# integrate.net
KiCad netlist of a schematic drawn in EAGLE
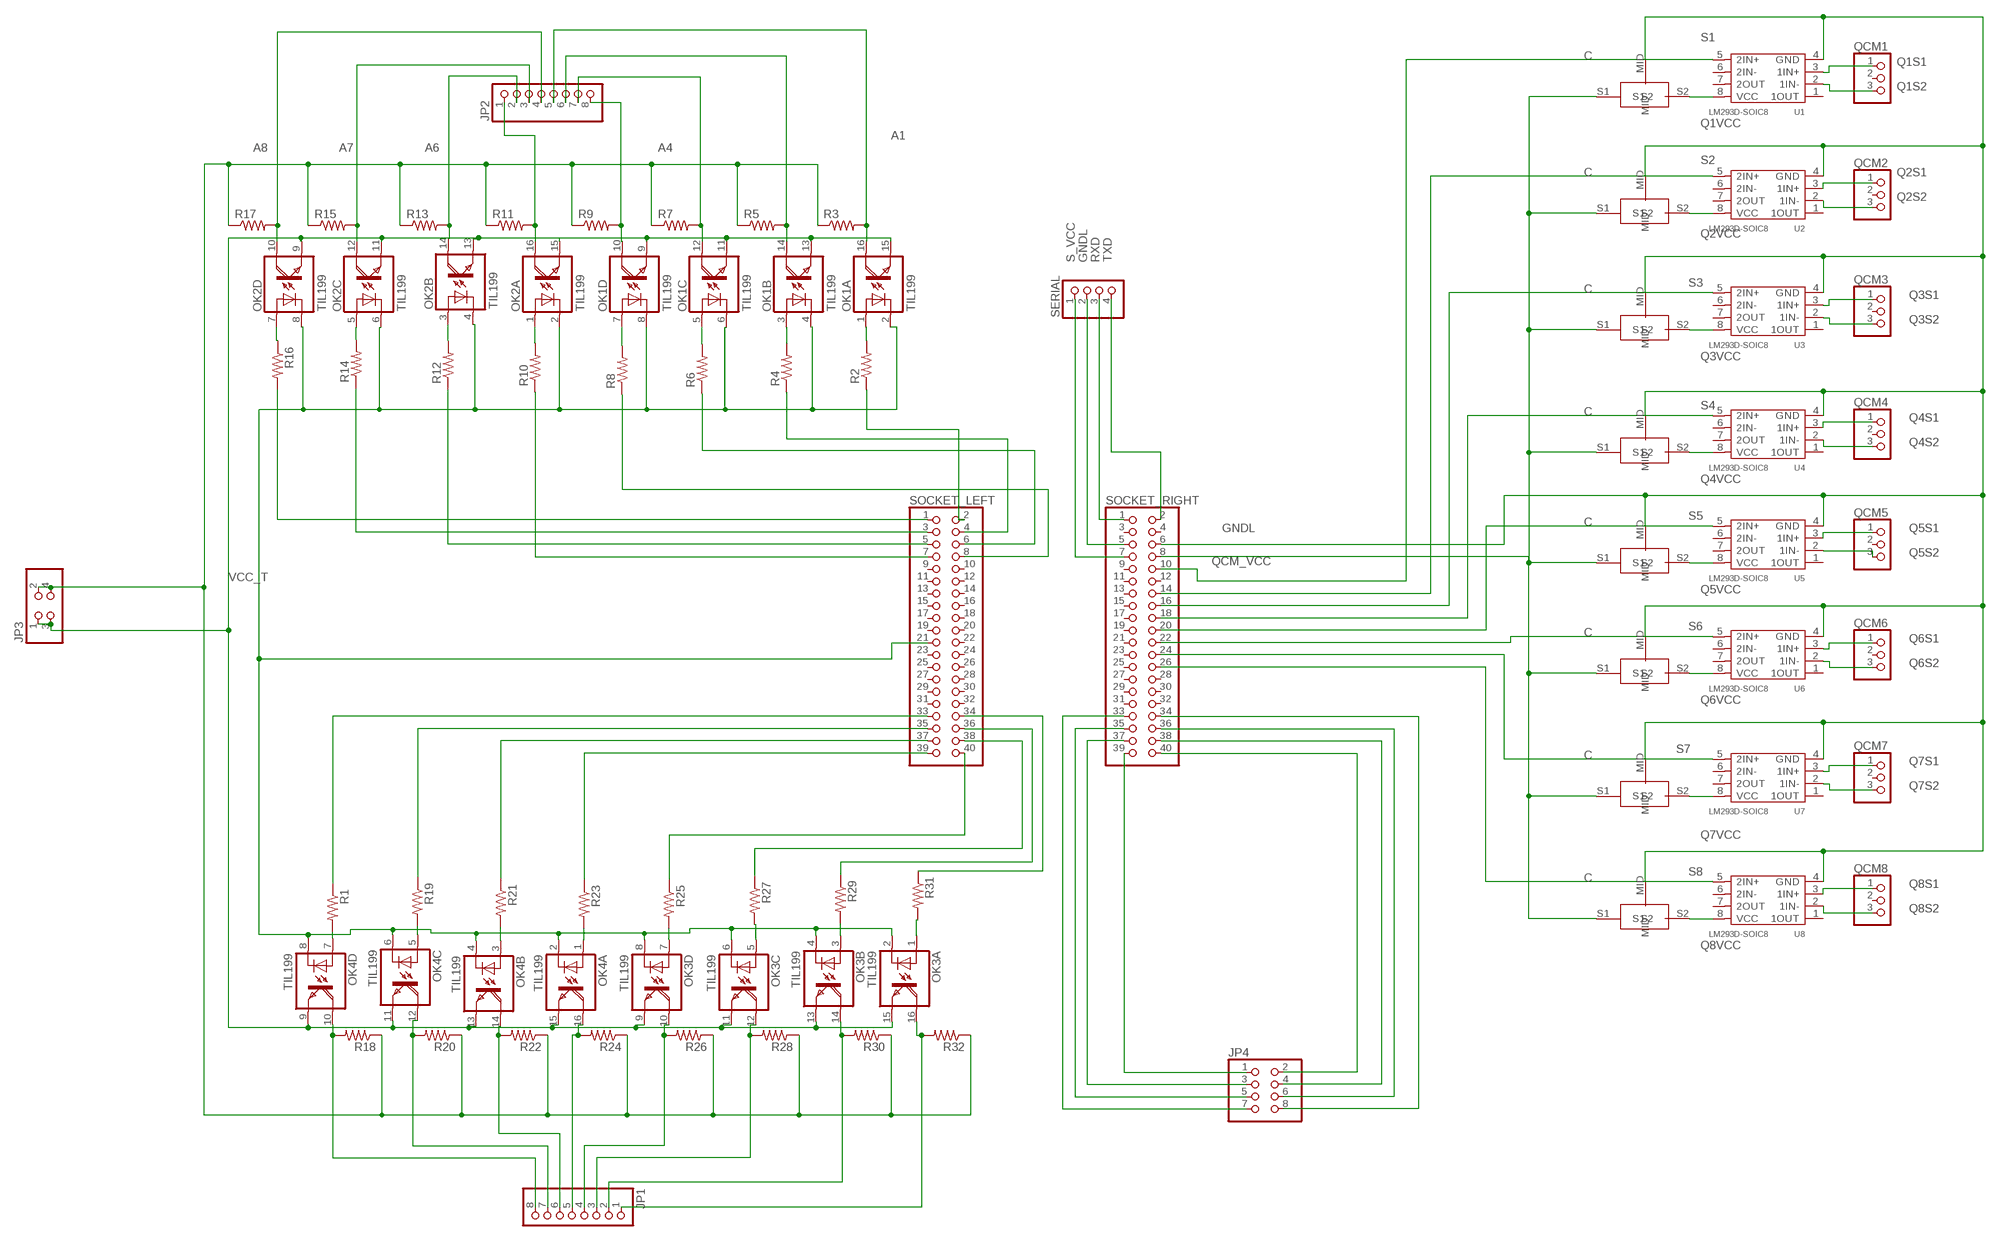
[diagram p0: schematic, sheet 1]

(export (version "E")
  (design (tool "Eeschema 10.0.6"))
  (components
    (comp (ref "JP1")
      (value "PINHD-1X8")
      (footprint "eagle-import:1X08")
      (libsource (lib "eagle-import") (part "PINHD-1X8"))
    )
    (comp (ref "JP2")
      (value "PINHD-1X8")
      (footprint "eagle-import:1X08")
      (libsource (lib "eagle-import") (part "PINHD-1X8"))
    )
    (comp (ref "JP3")
      (value "PINHD-2X2")
      (footprint "eagle-import:2X02")
      (libsource (lib "eagle-import") (part "PINHD-2X2"))
    )
    (comp (ref "JP4")
      (value "PINHD-2X4")
      (footprint "eagle-import:2X04")
      (libsource (lib "eagle-import") (part "PINHD-2X4"))
    )
    (comp (ref "OK1")
      (value "TIL199")
      (footprint "eagle-import:DIL16")
      (fields (field (name "MPN") "TIL 199"))
      (libsource (lib "eagle-import") (part "TIL199"))
    )
    (comp (ref "OK2")
      (value "TIL199")
      (footprint "eagle-import:DIL16")
      (fields (field (name "MPN") "TIL 199"))
      (libsource (lib "eagle-import") (part "TIL199"))
    )
    (comp (ref "OK3")
      (value "TIL199")
      (footprint "eagle-import:DIL16")
      (fields (field (name "MPN") "TIL 199"))
      (libsource (lib "eagle-import") (part "TIL199"))
    )
    (comp (ref "OK4")
      (value "TIL199")
      (footprint "eagle-import:DIL16")
      (fields (field (name "MPN") "TIL 199"))
      (libsource (lib "eagle-import") (part "TIL199"))
    )
    (comp (ref "OSCILLATOR3")
      (value "CSMD")
      (footprint "eagle-import:C")
      (libsource (lib "eagle-import") (part "CSMD"))
    )
    (comp (ref "OSCILLATOR4")
      (value "CSMD")
      (footprint "eagle-import:C")
      (libsource (lib "eagle-import") (part "CSMD"))
    )
    (comp (ref "OSCILLATOR5")
      (value "CSMD")
      (footprint "eagle-import:C")
      (libsource (lib "eagle-import") (part "CSMD"))
    )
    (comp (ref "OSCILLATOR6")
      (value "CSMD")
      (footprint "eagle-import:C")
      (libsource (lib "eagle-import") (part "CSMD"))
    )
    (comp (ref "OSCILLATOR7")
      (value "CSMD")
      (footprint "eagle-import:C")
      (libsource (lib "eagle-import") (part "CSMD"))
    )
    (comp (ref "OSCILLATOR8")
      (value "CSMD")
      (footprint "eagle-import:C")
      (libsource (lib "eagle-import") (part "CSMD"))
    )
    (comp (ref "OSCILLATOR9")
      (value "CSMD")
      (footprint "eagle-import:C")
      (libsource (lib "eagle-import") (part "CSMD"))
    )
    (comp (ref "OSCILLATOR10")
      (value "CSMD")
      (footprint "eagle-import:C")
      (libsource (lib "eagle-import") (part "CSMD"))
    )
    (comp (ref "QCM1")
      (value "PINHD-1X3")
      (footprint "eagle-import:1X03")
      (libsource (lib "eagle-import") (part "PINHD-1X3"))
    )
    (comp (ref "QCM2")
      (value "PINHD-1X3")
      (footprint "eagle-import:1X03")
      (libsource (lib "eagle-import") (part "PINHD-1X3"))
    )
    (comp (ref "QCM3")
      (value "PINHD-1X3")
      (footprint "eagle-import:1X03")
      (libsource (lib "eagle-import") (part "PINHD-1X3"))
    )
    (comp (ref "QCM4")
      (value "PINHD-1X3")
      (footprint "eagle-import:1X03")
      (libsource (lib "eagle-import") (part "PINHD-1X3"))
    )
    (comp (ref "QCM5")
      (value "PINHD-1X3")
      (footprint "eagle-import:1X03")
      (libsource (lib "eagle-import") (part "PINHD-1X3"))
    )
    (comp (ref "QCM6")
      (value "PINHD-1X3")
      (footprint "eagle-import:1X03")
      (libsource (lib "eagle-import") (part "PINHD-1X3"))
    )
    (comp (ref "QCM7")
      (value "PINHD-1X3")
      (footprint "eagle-import:1X03")
      (libsource (lib "eagle-import") (part "PINHD-1X3"))
    )
    (comp (ref "QCM8")
      (value "PINHD-1X3")
      (footprint "eagle-import:1X03")
      (libsource (lib "eagle-import") (part "PINHD-1X3"))
    )
    (comp (ref "R1")
      (value "R-US_0204/7")
      (footprint "eagle-import:0204_7")
      (libsource (lib "eagle-import") (part "R-US_0204/7"))
    )
    (comp (ref "R2")
      (value "R-US_0204/7")
      (footprint "eagle-import:0204_7")
      (libsource (lib "eagle-import") (part "R-US_0204/7"))
    )
    (comp (ref "R3")
      (value "R-US_0204/7")
      (footprint "eagle-import:0204_7")
      (libsource (lib "eagle-import") (part "R-US_0204/7"))
    )
    (comp (ref "R4")
      (value "R-US_0204/7")
      (footprint "eagle-import:0204_7")
      (libsource (lib "eagle-import") (part "R-US_0204/7"))
    )
    (comp (ref "R5")
      (value "R-US_0204/7")
      (footprint "eagle-import:0204_7")
      (libsource (lib "eagle-import") (part "R-US_0204/7"))
    )
    (comp (ref "R6")
      (value "R-US_0204/7")
      (footprint "eagle-import:0204_7")
      (libsource (lib "eagle-import") (part "R-US_0204/7"))
    )
    (comp (ref "R7")
      (value "R-US_0204/7")
      (footprint "eagle-import:0204_7")
      (libsource (lib "eagle-import") (part "R-US_0204/7"))
    )
    (comp (ref "R8")
      (value "R-US_0204/7")
      (footprint "eagle-import:0204_7")
      (libsource (lib "eagle-import") (part "R-US_0204/7"))
    )
    (comp (ref "R9")
      (value "R-US_0204/7")
      (footprint "eagle-import:0204_7")
      (libsource (lib "eagle-import") (part "R-US_0204/7"))
    )
    (comp (ref "R10")
      (value "R-US_0204/7")
      (footprint "eagle-import:0204_7")
      (libsource (lib "eagle-import") (part "R-US_0204/7"))
    )
    (comp (ref "R11")
      (value "R-US_0204/7")
      (footprint "eagle-import:0204_7")
      (libsource (lib "eagle-import") (part "R-US_0204/7"))
    )
    (comp (ref "R12")
      (value "R-US_0204/7")
      (footprint "eagle-import:0204_7")
      (libsource (lib "eagle-import") (part "R-US_0204/7"))
    )
    (comp (ref "R13")
      (value "R-US_0204/7")
      (footprint "eagle-import:0204_7")
      (libsource (lib "eagle-import") (part "R-US_0204/7"))
    )
    (comp (ref "R14")
      (value "R-US_0204/7")
      (footprint "eagle-import:0204_7")
      (libsource (lib "eagle-import") (part "R-US_0204/7"))
    )
    (comp (ref "R15")
      (value "R-US_0204/7")
      (footprint "eagle-import:0204_7")
      (libsource (lib "eagle-import") (part "R-US_0204/7"))
    )
    (comp (ref "R16")
      (value "R-US_0204/7")
      (footprint "eagle-import:0204_7")
      (libsource (lib "eagle-import") (part "R-US_0204/7"))
    )
    (comp (ref "R17")
      (value "R-US_0204/7")
      (footprint "eagle-import:0204_7")
      (libsource (lib "eagle-import") (part "R-US_0204/7"))
    )
    (comp (ref "R18")
      (value "R-US_0204/7")
      (footprint "eagle-import:0204_7")
      (libsource (lib "eagle-import") (part "R-US_0204/7"))
    )
    (comp (ref "R19")
      (value "R-US_0204/7")
      (footprint "eagle-import:0204_7")
      (libsource (lib "eagle-import") (part "R-US_0204/7"))
    )
    (comp (ref "R20")
      (value "R-US_0204/7")
      (footprint "eagle-import:0204_7")
      (libsource (lib "eagle-import") (part "R-US_0204/7"))
    )
    (comp (ref "R21")
      (value "R-US_0204/7")
      (footprint "eagle-import:0204_7")
      (libsource (lib "eagle-import") (part "R-US_0204/7"))
    )
    (comp (ref "R22")
      (value "R-US_0204/7")
      (footprint "eagle-import:0204_7")
      (libsource (lib "eagle-import") (part "R-US_0204/7"))
    )
    (comp (ref "R23")
      (value "R-US_0204/7")
      (footprint "eagle-import:0204_7")
      (libsource (lib "eagle-import") (part "R-US_0204/7"))
    )
    (comp (ref "R24")
      (value "R-US_0204/7")
      (footprint "eagle-import:0204_7")
      (libsource (lib "eagle-import") (part "R-US_0204/7"))
    )
    (comp (ref "R25")
      (value "R-US_0204/7")
      (footprint "eagle-import:0204_7")
      (libsource (lib "eagle-import") (part "R-US_0204/7"))
    )
    (comp (ref "R26")
      (value "R-US_0204/7")
      (footprint "eagle-import:0204_7")
      (libsource (lib "eagle-import") (part "R-US_0204/7"))
    )
    (comp (ref "R27")
      (value "R-US_0204/7")
      (footprint "eagle-import:0204_7")
      (libsource (lib "eagle-import") (part "R-US_0204/7"))
    )
    (comp (ref "R28")
      (value "R-US_0204/7")
      (footprint "eagle-import:0204_7")
      (libsource (lib "eagle-import") (part "R-US_0204/7"))
    )
    (comp (ref "R29")
      (value "R-US_0204/7")
      (footprint "eagle-import:0204_7")
      (libsource (lib "eagle-import") (part "R-US_0204/7"))
    )
    (comp (ref "R30")
      (value "R-US_0204/7")
      (footprint "eagle-import:0204_7")
      (libsource (lib "eagle-import") (part "R-US_0204/7"))
    )
    (comp (ref "R31")
      (value "R-US_0204/7")
      (footprint "eagle-import:0204_7")
      (libsource (lib "eagle-import") (part "R-US_0204/7"))
    )
    (comp (ref "R32")
      (value "R-US_0204/7")
      (footprint "eagle-import:0204_7")
      (libsource (lib "eagle-import") (part "R-US_0204/7"))
    )
    (comp (ref "SERIAL")
      (value "PINHD-1X4")
      (footprint "eagle-import:1X04")
      (libsource (lib "eagle-import") (part "PINHD-1X4"))
    )
    (comp (ref "SOCKET_LEFT")
      (value "PINHD-2X20")
      (footprint "eagle-import:2X20")
      (libsource (lib "eagle-import") (part "PINHD-2X20"))
    )
    (comp (ref "SOCKET_RIGHT")
      (value "PINHD-2X20")
      (footprint "eagle-import:2X20")
      (libsource (lib "eagle-import") (part "PINHD-2X20"))
    )
    (comp (ref "U1")
      (value "LM293D-SOIC8")
      (footprint "eagle-import:SOIC8-1.27-5X4MM")
      (fields (field (name "MPN") "LM293D"))
      (libsource (lib "eagle-import") (part "AMPLIFIER-LM293D(SOIC8)"))
    )
    (comp (ref "U2")
      (value "LM293D-SOIC8")
      (footprint "eagle-import:SOIC8-1.27-5X4MM")
      (fields (field (name "MPN") "LM293D"))
      (libsource (lib "eagle-import") (part "AMPLIFIER-LM293D(SOIC8)"))
    )
    (comp (ref "U3")
      (value "LM293D-SOIC8")
      (footprint "eagle-import:SOIC8-1.27-5X4MM")
      (fields (field (name "MPN") "LM293D"))
      (libsource (lib "eagle-import") (part "AMPLIFIER-LM293D(SOIC8)"))
    )
    (comp (ref "U4")
      (value "LM293D-SOIC8")
      (footprint "eagle-import:SOIC8-1.27-5X4MM")
      (fields (field (name "MPN") "LM293D"))
      (libsource (lib "eagle-import") (part "AMPLIFIER-LM293D(SOIC8)"))
    )
    (comp (ref "U5")
      (value "LM293D-SOIC8")
      (footprint "eagle-import:SOIC8-1.27-5X4MM")
      (fields (field (name "MPN") "LM293D"))
      (libsource (lib "eagle-import") (part "AMPLIFIER-LM293D(SOIC8)"))
    )
    (comp (ref "U6")
      (value "LM293D-SOIC8")
      (footprint "eagle-import:SOIC8-1.27-5X4MM")
      (fields (field (name "MPN") "LM293D"))
      (libsource (lib "eagle-import") (part "AMPLIFIER-LM293D(SOIC8)"))
    )
    (comp (ref "U7")
      (value "LM293D-SOIC8")
      (footprint "eagle-import:SOIC8-1.27-5X4MM")
      (fields (field (name "MPN") "LM293D"))
      (libsource (lib "eagle-import") (part "AMPLIFIER-LM293D(SOIC8)"))
    )
    (comp (ref "U8")
      (value "LM293D-SOIC8")
      (footprint "eagle-import:SOIC8-1.27-5X4MM")
      (fields (field (name "MPN") "LM293D"))
      (libsource (lib "eagle-import") (part "AMPLIFIER-LM293D(SOIC8)"))
    )
  )
  (nets
    (net (code "1") (name "/A1") (class "Default")
      (node (ref "JP2") (pin "5") (pinfunction "5_5") (pintype "passive"))
      (node (ref "OK1") (pin "16") (pinfunction "COL_16") (pintype "passive"))
      (node (ref "R3") (pin "2") (pinfunction "2_2") (pintype "passive"))
    )
    (net (code "2") (name "/A4") (class "Default")
      (node (ref "JP2") (pin "8") (pinfunction "8_8") (pintype "passive"))
      (node (ref "OK1") (pin "10") (pinfunction "COL_10") (pintype "passive"))
      (node (ref "R9") (pin "2") (pinfunction "2_2") (pintype "passive"))
    )
    (net (code "3") (name "/A6") (class "Default")
      (node (ref "JP2") (pin "2") (pinfunction "2_2") (pintype "passive"))
      (node (ref "OK2") (pin "14") (pinfunction "COL_14") (pintype "passive"))
      (node (ref "R13") (pin "2") (pinfunction "2_2") (pintype "passive"))
    )
    (net (code "4") (name "/A7") (class "Default")
      (node (ref "JP2") (pin "3") (pinfunction "3_3") (pintype "passive"))
      (node (ref "OK2") (pin "12") (pinfunction "COL_12") (pintype "passive"))
      (node (ref "R15") (pin "2") (pinfunction "2_2") (pintype "passive"))
    )
    (net (code "5") (name "/A8") (class "Default")
      (node (ref "JP2") (pin "4") (pinfunction "4_4") (pintype "passive"))
      (node (ref "OK2") (pin "10") (pinfunction "COL_10") (pintype "passive"))
      (node (ref "R17") (pin "2") (pinfunction "2_2") (pintype "passive"))
    )
    (net (code "6") (name "/GNDL") (class "Default")
      (node (ref "OK1") (pin "2") (pinfunction "C_2") (pintype "passive"))
      (node (ref "OK1") (pin "4") (pinfunction "C_4") (pintype "passive"))
      (node (ref "OK1") (pin "6") (pinfunction "C_6") (pintype "passive"))
      (node (ref "OK1") (pin "8") (pinfunction "C_8") (pintype "passive"))
      (node (ref "OK2") (pin "2") (pinfunction "C_2") (pintype "passive"))
      (node (ref "OK2") (pin "4") (pinfunction "C_4") (pintype "passive"))
      (node (ref "OK2") (pin "6") (pinfunction "C_6") (pintype "passive"))
      (node (ref "OK2") (pin "8") (pinfunction "C_8") (pintype "passive"))
      (node (ref "OK3") (pin "2") (pinfunction "C_2") (pintype "passive"))
      (node (ref "OK3") (pin "4") (pinfunction "C_4") (pintype "passive"))
      (node (ref "OK3") (pin "6") (pinfunction "C_6") (pintype "passive"))
      (node (ref "OK3") (pin "8") (pinfunction "C_8") (pintype "passive"))
      (node (ref "OK4") (pin "2") (pinfunction "C_2") (pintype "passive"))
      (node (ref "OK4") (pin "4") (pinfunction "C_4") (pintype "passive"))
      (node (ref "OK4") (pin "6") (pinfunction "C_6") (pintype "passive"))
      (node (ref "OK4") (pin "8") (pinfunction "C_8") (pintype "passive"))
      (node (ref "OSCILLATOR10") (pin "MID") (pinfunction "MID_MID") (pintype "bidirectional"))
      (node (ref "OSCILLATOR3") (pin "MID") (pinfunction "MID_MID") (pintype "bidirectional"))
      (node (ref "OSCILLATOR4") (pin "MID") (pinfunction "MID_MID") (pintype "bidirectional"))
      (node (ref "OSCILLATOR5") (pin "MID") (pinfunction "MID_MID") (pintype "bidirectional"))
      (node (ref "OSCILLATOR6") (pin "MID") (pinfunction "MID_MID") (pintype "bidirectional"))
      (node (ref "OSCILLATOR7") (pin "MID") (pinfunction "MID_MID") (pintype "bidirectional"))
      (node (ref "OSCILLATOR8") (pin "MID") (pinfunction "MID_MID") (pintype "bidirectional"))
      (node (ref "OSCILLATOR9") (pin "MID") (pinfunction "MID_MID") (pintype "bidirectional"))
      (node (ref "SERIAL") (pin "2") (pinfunction "2_2") (pintype "passive"))
      (node (ref "SOCKET_LEFT") (pin "21") (pinfunction "21_21") (pintype "passive"))
      (node (ref "SOCKET_RIGHT") (pin "5") (pinfunction "5_5") (pintype "passive"))
      (node (ref "SOCKET_RIGHT") (pin "6") (pinfunction "6_6") (pintype "passive"))
      (node (ref "U1") (pin "4") (pinfunction "GND_4") (pintype "power_in"))
      (node (ref "U2") (pin "4") (pinfunction "GND_4") (pintype "power_in"))
      (node (ref "U3") (pin "4") (pinfunction "GND_4") (pintype "power_in"))
      (node (ref "U4") (pin "4") (pinfunction "GND_4") (pintype "power_in"))
      (node (ref "U5") (pin "4") (pinfunction "GND_4") (pintype "power_in"))
      (node (ref "U6") (pin "4") (pinfunction "GND_4") (pintype "power_in"))
      (node (ref "U7") (pin "4") (pinfunction "GND_4") (pintype "power_in"))
      (node (ref "U8") (pin "4") (pinfunction "GND_4") (pintype "power_in"))
    )
    (net (code "7") (name "/Q1S1") (class "Default")
      (node (ref "QCM1") (pin "1") (pinfunction "1_1") (pintype "passive"))
      (node (ref "U1") (pin "3") (pinfunction "1IN+_3") (pintype "input"))
    )
    (net (code "8") (name "/Q1S2") (class "Default")
      (node (ref "QCM1") (pin "3") (pinfunction "3_3") (pintype "passive"))
      (node (ref "U1") (pin "2") (pinfunction "1IN-_2") (pintype "input"))
    )
    (net (code "9") (name "/Q1VCC") (class "Default")
      (node (ref "OSCILLATOR3") (pin "S2") (pinfunction "S2_S2") (pintype "bidirectional"))
      (node (ref "U1") (pin "8") (pinfunction "VCC_8") (pintype "power_in"))
    )
    (net (code "10") (name "/Q2S1") (class "Default")
      (node (ref "QCM2") (pin "1") (pinfunction "1_1") (pintype "passive"))
      (node (ref "U2") (pin "3") (pinfunction "1IN+_3") (pintype "input"))
    )
    (net (code "11") (name "/Q2S2") (class "Default")
      (node (ref "QCM2") (pin "3") (pinfunction "3_3") (pintype "passive"))
      (node (ref "U2") (pin "2") (pinfunction "1IN-_2") (pintype "input"))
    )
    (net (code "12") (name "/Q2VCC") (class "Default")
      (node (ref "OSCILLATOR4") (pin "S2") (pinfunction "S2_S2") (pintype "bidirectional"))
      (node (ref "U2") (pin "8") (pinfunction "VCC_8") (pintype "power_in"))
    )
    (net (code "13") (name "/Q3S1") (class "Default")
      (node (ref "QCM3") (pin "1") (pinfunction "1_1") (pintype "passive"))
      (node (ref "U3") (pin "3") (pinfunction "1IN+_3") (pintype "input"))
    )
    (net (code "14") (name "/Q3S2") (class "Default")
      (node (ref "QCM3") (pin "3") (pinfunction "3_3") (pintype "passive"))
      (node (ref "U3") (pin "2") (pinfunction "1IN-_2") (pintype "input"))
    )
    (net (code "15") (name "/Q3VCC") (class "Default")
      (node (ref "OSCILLATOR5") (pin "S2") (pinfunction "S2_S2") (pintype "bidirectional"))
      (node (ref "U3") (pin "8") (pinfunction "VCC_8") (pintype "power_in"))
    )
    (net (code "16") (name "/Q4S1") (class "Default")
      (node (ref "QCM4") (pin "1") (pinfunction "1_1") (pintype "passive"))
      (node (ref "U4") (pin "3") (pinfunction "1IN+_3") (pintype "input"))
    )
    (net (code "17") (name "/Q4S2") (class "Default")
      (node (ref "QCM4") (pin "3") (pinfunction "3_3") (pintype "passive"))
      (node (ref "U4") (pin "2") (pinfunction "1IN-_2") (pintype "input"))
    )
    (net (code "18") (name "/Q4VCC") (class "Default")
      (node (ref "OSCILLATOR6") (pin "S2") (pinfunction "S2_S2") (pintype "bidirectional"))
      (node (ref "U4") (pin "8") (pinfunction "VCC_8") (pintype "power_in"))
    )
    (net (code "19") (name "/Q5S1") (class "Default")
      (node (ref "QCM5") (pin "1") (pinfunction "1_1") (pintype "passive"))
      (node (ref "U5") (pin "3") (pinfunction "1IN+_3") (pintype "input"))
    )
    (net (code "20") (name "/Q5S2") (class "Default")
      (node (ref "QCM5") (pin "3") (pinfunction "3_3") (pintype "passive"))
      (node (ref "U5") (pin "2") (pinfunction "1IN-_2") (pintype "input"))
    )
    (net (code "21") (name "/Q5VCC") (class "Default")
      (node (ref "OSCILLATOR7") (pin "S2") (pinfunction "S2_S2") (pintype "bidirectional"))
      (node (ref "U5") (pin "8") (pinfunction "VCC_8") (pintype "power_in"))
    )
    (net (code "22") (name "/Q6S1") (class "Default")
      (node (ref "QCM6") (pin "1") (pinfunction "1_1") (pintype "passive"))
      (node (ref "U6") (pin "3") (pinfunction "1IN+_3") (pintype "input"))
    )
    (net (code "23") (name "/Q6S2") (class "Default")
      (node (ref "QCM6") (pin "3") (pinfunction "3_3") (pintype "passive"))
      (node (ref "U6") (pin "2") (pinfunction "1IN-_2") (pintype "input"))
    )
    (net (code "24") (name "/Q6VCC") (class "Default")
      (node (ref "OSCILLATOR8") (pin "S2") (pinfunction "S2_S2") (pintype "bidirectional"))
      (node (ref "U6") (pin "8") (pinfunction "VCC_8") (pintype "power_in"))
    )
    (net (code "25") (name "/Q7S1") (class "Default")
      (node (ref "QCM7") (pin "1") (pinfunction "1_1") (pintype "passive"))
      (node (ref "U7") (pin "3") (pinfunction "1IN+_3") (pintype "input"))
    )
    (net (code "26") (name "/Q7S2") (class "Default")
      (node (ref "QCM7") (pin "3") (pinfunction "3_3") (pintype "passive"))
      (node (ref "U7") (pin "2") (pinfunction "1IN-_2") (pintype "input"))
    )
    (net (code "27") (name "/Q7VCC") (class "Default")
      (node (ref "OSCILLATOR9") (pin "S2") (pinfunction "S2_S2") (pintype "bidirectional"))
      (node (ref "U7") (pin "8") (pinfunction "VCC_8") (pintype "power_in"))
    )
    (net (code "28") (name "/Q8S1") (class "Default")
      (node (ref "QCM8") (pin "1") (pinfunction "1_1") (pintype "passive"))
      (node (ref "U8") (pin "3") (pinfunction "1IN+_3") (pintype "input"))
    )
    (net (code "29") (name "/Q8S2") (class "Default")
      (node (ref "QCM8") (pin "3") (pinfunction "3_3") (pintype "passive"))
      (node (ref "U8") (pin "2") (pinfunction "1IN-_2") (pintype "input"))
    )
    (net (code "30") (name "/Q8VCC") (class "Default")
      (node (ref "OSCILLATOR10") (pin "S2") (pinfunction "S2_S2") (pintype "bidirectional"))
      (node (ref "U8") (pin "8") (pinfunction "VCC_8") (pintype "power_in"))
    )
    (net (code "31") (name "/QCM_VCC") (class "Default")
      (node (ref "OSCILLATOR10") (pin "S1") (pinfunction "S1_S1") (pintype "bidirectional"))
      (node (ref "OSCILLATOR3") (pin "S1") (pinfunction "S1_S1") (pintype "bidirectional"))
      (node (ref "OSCILLATOR4") (pin "S1") (pinfunction "S1_S1") (pintype "bidirectional"))
      (node (ref "OSCILLATOR5") (pin "S1") (pinfunction "S1_S1") (pintype "bidirectional"))
      (node (ref "OSCILLATOR6") (pin "S1") (pinfunction "S1_S1") (pintype "bidirectional"))
      (node (ref "OSCILLATOR7") (pin "S1") (pinfunction "S1_S1") (pintype "bidirectional"))
      (node (ref "OSCILLATOR8") (pin "S1") (pinfunction "S1_S1") (pintype "bidirectional"))
      (node (ref "OSCILLATOR9") (pin "S1") (pinfunction "S1_S1") (pintype "bidirectional"))
      (node (ref "SOCKET_RIGHT") (pin "8") (pinfunction "8_8") (pintype "passive"))
    )
    (net (code "32") (name "/RXD") (class "Default")
      (node (ref "SERIAL") (pin "3") (pinfunction "3_3") (pintype "passive"))
      (node (ref "SOCKET_RIGHT") (pin "1") (pinfunction "1_1") (pintype "passive"))
    )
    (net (code "33") (name "/S1") (class "Default")
      (node (ref "SOCKET_RIGHT") (pin "10") (pinfunction "10_10") (pintype "passive"))
      (node (ref "U1") (pin "5") (pinfunction "2IN+_5") (pintype "input"))
    )
    (net (code "34") (name "/S2") (class "Default")
      (node (ref "SOCKET_RIGHT") (pin "14") (pinfunction "14_14") (pintype "passive"))
      (node (ref "U2") (pin "5") (pinfunction "2IN+_5") (pintype "input"))
    )
    (net (code "35") (name "/S3") (class "Default")
      (node (ref "SOCKET_RIGHT") (pin "16") (pinfunction "16_16") (pintype "passive"))
      (node (ref "U3") (pin "5") (pinfunction "2IN+_5") (pintype "input"))
    )
    (net (code "36") (name "/S4") (class "Default")
      (node (ref "SOCKET_RIGHT") (pin "18") (pinfunction "18_18") (pintype "passive"))
      (node (ref "U4") (pin "5") (pinfunction "2IN+_5") (pintype "input"))
    )
    (net (code "37") (name "/S5") (class "Default")
      (node (ref "SOCKET_RIGHT") (pin "20") (pinfunction "20_20") (pintype "passive"))
      (node (ref "U5") (pin "5") (pinfunction "2IN+_5") (pintype "input"))
    )
    (net (code "38") (name "/S6") (class "Default")
      (node (ref "SOCKET_RIGHT") (pin "22") (pinfunction "22_22") (pintype "passive"))
      (node (ref "U6") (pin "5") (pinfunction "2IN+_5") (pintype "input"))
    )
    (net (code "39") (name "/S7") (class "Default")
      (node (ref "SOCKET_RIGHT") (pin "24") (pinfunction "24_24") (pintype "passive"))
      (node (ref "U7") (pin "5") (pinfunction "2IN+_5") (pintype "input"))
    )
    (net (code "40") (name "/S8") (class "Default")
      (node (ref "SOCKET_RIGHT") (pin "26") (pinfunction "26_26") (pintype "passive"))
      (node (ref "U8") (pin "5") (pinfunction "2IN+_5") (pintype "input"))
    )
    (net (code "41") (name "/S_VCC") (class "Default")
      (node (ref "SERIAL") (pin "1") (pinfunction "1_1") (pintype "passive"))
      (node (ref "SOCKET_RIGHT") (pin "7") (pinfunction "7_7") (pintype "passive"))
    )
    (net (code "42") (name "/TXD") (class "Default")
      (node (ref "SERIAL") (pin "4") (pinfunction "4_4") (pintype "passive"))
      (node (ref "SOCKET_RIGHT") (pin "2") (pinfunction "2_2") (pintype "passive"))
    )
    (net (code "43") (name "/VCC_T") (class "Default")
      (node (ref "JP3") (pin "2") (pinfunction "2_2") (pintype "passive"))
      (node (ref "JP3") (pin "4") (pinfunction "4_4") (pintype "passive"))
      (node (ref "R11") (pin "1") (pinfunction "1_1") (pintype "passive"))
      (node (ref "R13") (pin "1") (pinfunction "1_1") (pintype "passive"))
      (node (ref "R15") (pin "1") (pinfunction "1_1") (pintype "passive"))
      (node (ref "R17") (pin "1") (pinfunction "1_1") (pintype "passive"))
      (node (ref "R18") (pin "1") (pinfunction "1_1") (pintype "passive"))
      (node (ref "R20") (pin "1") (pinfunction "1_1") (pintype "passive"))
      (node (ref "R22") (pin "1") (pinfunction "1_1") (pintype "passive"))
      (node (ref "R24") (pin "1") (pinfunction "1_1") (pintype "passive"))
      (node (ref "R26") (pin "1") (pinfunction "1_1") (pintype "passive"))
      (node (ref "R28") (pin "1") (pinfunction "1_1") (pintype "passive"))
      (node (ref "R3") (pin "1") (pinfunction "1_1") (pintype "passive"))
      (node (ref "R30") (pin "1") (pinfunction "1_1") (pintype "passive"))
      (node (ref "R32") (pin "1") (pinfunction "1_1") (pintype "passive"))
      (node (ref "R5") (pin "1") (pinfunction "1_1") (pintype "passive"))
      (node (ref "R7") (pin "1") (pinfunction "1_1") (pintype "passive"))
      (node (ref "R9") (pin "1") (pinfunction "1_1") (pintype "passive"))
    )
    (net (code "44") (name "Net-(JP4-Pad1)") (class "Default")
      (node (ref "JP4") (pin "1") (pinfunction "1_1") (pintype "passive"))
      (node (ref "SOCKET_RIGHT") (pin "39") (pinfunction "39_39") (pintype "passive"))
    )
    (net (code "45") (name "Net-(JP4-Pad2)") (class "Default")
      (node (ref "JP4") (pin "2") (pinfunction "2_2") (pintype "passive"))
      (node (ref "SOCKET_RIGHT") (pin "40") (pinfunction "40_40") (pintype "passive"))
    )
    (net (code "46") (name "Net-(JP4-Pad3)") (class "Default")
      (node (ref "JP4") (pin "3") (pinfunction "3_3") (pintype "passive"))
      (node (ref "SOCKET_RIGHT") (pin "37") (pinfunction "37_37") (pintype "passive"))
    )
    (net (code "47") (name "Net-(JP4-Pad4)") (class "Default")
      (node (ref "JP4") (pin "4") (pinfunction "4_4") (pintype "passive"))
      (node (ref "SOCKET_RIGHT") (pin "38") (pinfunction "38_38") (pintype "passive"))
    )
    (net (code "48") (name "Net-(JP4-Pad5)") (class "Default")
      (node (ref "JP4") (pin "5") (pinfunction "5_5") (pintype "passive"))
      (node (ref "SOCKET_RIGHT") (pin "35") (pinfunction "35_35") (pintype "passive"))
    )
    (net (code "49") (name "Net-(JP4-Pad6)") (class "Default")
      (node (ref "JP4") (pin "6") (pinfunction "6_6") (pintype "passive"))
      (node (ref "SOCKET_RIGHT") (pin "36") (pinfunction "36_36") (pintype "passive"))
    )
    (net (code "50") (name "Net-(JP4-Pad7)") (class "Default")
      (node (ref "JP4") (pin "7") (pinfunction "7_7") (pintype "passive"))
      (node (ref "SOCKET_RIGHT") (pin "33") (pinfunction "33_33") (pintype "passive"))
    )
    (net (code "51") (name "Net-(JP4-Pad8)") (class "Default")
      (node (ref "JP4") (pin "8") (pinfunction "8_8") (pintype "passive"))
      (node (ref "SOCKET_RIGHT") (pin "34") (pinfunction "34_34") (pintype "passive"))
    )
    (net (code "52") (name "Net-(OK1A-A)") (class "Default")
      (node (ref "OK1") (pin "1") (pinfunction "A_1") (pintype "passive"))
      (node (ref "R2") (pin "2") (pinfunction "2_2") (pintype "passive"))
    )
    (net (code "53") (name "Net-(OK1A-EMI)") (class "Default")
      (node (ref "JP3") (pin "1") (pinfunction "1_1") (pintype "passive"))
      (node (ref "JP3") (pin "3") (pinfunction "3_3") (pintype "passive"))
      (node (ref "OK1") (pin "11") (pinfunction "EMI_11") (pintype "passive"))
      (node (ref "OK1") (pin "13") (pinfunction "EMI_13") (pintype "passive"))
      (node (ref "OK1") (pin "15") (pinfunction "EMI_15") (pintype "passive"))
      (node (ref "OK1") (pin "9") (pinfunction "EMI_9") (pintype "passive"))
      (node (ref "OK2") (pin "11") (pinfunction "EMI_11") (pintype "passive"))
      (node (ref "OK2") (pin "13") (pinfunction "EMI_13") (pintype "passive"))
      (node (ref "OK2") (pin "15") (pinfunction "EMI_15") (pintype "passive"))
      (node (ref "OK2") (pin "9") (pinfunction "EMI_9") (pintype "passive"))
      (node (ref "OK3") (pin "11") (pinfunction "EMI_11") (pintype "passive"))
      (node (ref "OK3") (pin "13") (pinfunction "EMI_13") (pintype "passive"))
      (node (ref "OK3") (pin "15") (pinfunction "EMI_15") (pintype "passive"))
      (node (ref "OK3") (pin "9") (pinfunction "EMI_9") (pintype "passive"))
      (node (ref "OK4") (pin "11") (pinfunction "EMI_11") (pintype "passive"))
      (node (ref "OK4") (pin "13") (pinfunction "EMI_13") (pintype "passive"))
      (node (ref "OK4") (pin "15") (pinfunction "EMI_15") (pintype "passive"))
      (node (ref "OK4") (pin "9") (pinfunction "EMI_9") (pintype "passive"))
    )
    (net (code "54") (name "Net-(OK1B-A)") (class "Default")
      (node (ref "OK1") (pin "3") (pinfunction "A_3") (pintype "passive"))
      (node (ref "R4") (pin "2") (pinfunction "2_2") (pintype "passive"))
    )
    (net (code "55") (name "Net-(OK1B-COL)") (class "Default")
      (node (ref "JP2") (pin "6") (pinfunction "6_6") (pintype "passive"))
      (node (ref "OK1") (pin "14") (pinfunction "COL_14") (pintype "passive"))
      (node (ref "R5") (pin "2") (pinfunction "2_2") (pintype "passive"))
    )
    (net (code "56") (name "Net-(OK1C-A)") (class "Default")
      (node (ref "OK1") (pin "5") (pinfunction "A_5") (pintype "passive"))
      (node (ref "R6") (pin "2") (pinfunction "2_2") (pintype "passive"))
    )
    (net (code "57") (name "Net-(OK1C-COL)") (class "Default")
      (node (ref "JP2") (pin "7") (pinfunction "7_7") (pintype "passive"))
      (node (ref "OK1") (pin "12") (pinfunction "COL_12") (pintype "passive"))
      (node (ref "R7") (pin "2") (pinfunction "2_2") (pintype "passive"))
    )
    (net (code "58") (name "Net-(OK1D-A)") (class "Default")
      (node (ref "OK1") (pin "7") (pinfunction "A_7") (pintype "passive"))
      (node (ref "R8") (pin "2") (pinfunction "2_2") (pintype "passive"))
    )
    (net (code "59") (name "Net-(OK2A-A)") (class "Default")
      (node (ref "OK2") (pin "1") (pinfunction "A_1") (pintype "passive"))
      (node (ref "R10") (pin "2") (pinfunction "2_2") (pintype "passive"))
    )
    (net (code "60") (name "Net-(OK2A-COL)") (class "Default")
      (node (ref "JP2") (pin "1") (pinfunction "1_1") (pintype "passive"))
      (node (ref "OK2") (pin "16") (pinfunction "COL_16") (pintype "passive"))
      (node (ref "R11") (pin "2") (pinfunction "2_2") (pintype "passive"))
    )
    (net (code "61") (name "Net-(OK2B-A)") (class "Default")
      (node (ref "OK2") (pin "3") (pinfunction "A_3") (pintype "passive"))
      (node (ref "R12") (pin "2") (pinfunction "2_2") (pintype "passive"))
    )
    (net (code "62") (name "Net-(OK2C-A)") (class "Default")
      (node (ref "OK2") (pin "5") (pinfunction "A_5") (pintype "passive"))
      (node (ref "R14") (pin "2") (pinfunction "2_2") (pintype "passive"))
    )
    (net (code "63") (name "Net-(OK2D-A)") (class "Default")
      (node (ref "OK2") (pin "7") (pinfunction "A_7") (pintype "passive"))
      (node (ref "R16") (pin "1") (pinfunction "1_1") (pintype "passive"))
    )
    (net (code "64") (name "Net-(OK3A-A)") (class "Default")
      (node (ref "OK3") (pin "1") (pinfunction "A_1") (pintype "passive"))
      (node (ref "R31") (pin "2") (pinfunction "2_2") (pintype "passive"))
    )
    (net (code "65") (name "Net-(OK3A-COL)") (class "Default")
      (node (ref "JP1") (pin "1") (pinfunction "1_1") (pintype "passive"))
      (node (ref "OK3") (pin "16") (pinfunction "COL_16") (pintype "passive"))
      (node (ref "R32") (pin "2") (pinfunction "2_2") (pintype "passive"))
    )
    (net (code "66") (name "Net-(OK3B-A)") (class "Default")
      (node (ref "OK3") (pin "3") (pinfunction "A_3") (pintype "passive"))
      (node (ref "R29") (pin "2") (pinfunction "2_2") (pintype "passive"))
    )
    (net (code "67") (name "Net-(OK3B-COL)") (class "Default")
      (node (ref "JP1") (pin "2") (pinfunction "2_2") (pintype "passive"))
      (node (ref "OK3") (pin "14") (pinfunction "COL_14") (pintype "passive"))
      (node (ref "R30") (pin "2") (pinfunction "2_2") (pintype "passive"))
    )
    (net (code "68") (name "Net-(OK3C-A)") (class "Default")
      (node (ref "OK3") (pin "5") (pinfunction "A_5") (pintype "passive"))
      (node (ref "R27") (pin "2") (pinfunction "2_2") (pintype "passive"))
    )
    (net (code "69") (name "Net-(OK3C-COL)") (class "Default")
      (node (ref "JP1") (pin "3") (pinfunction "3_3") (pintype "passive"))
      (node (ref "OK3") (pin "12") (pinfunction "COL_12") (pintype "passive"))
      (node (ref "R28") (pin "2") (pinfunction "2_2") (pintype "passive"))
    )
    (net (code "70") (name "Net-(OK3D-A)") (class "Default")
      (node (ref "OK3") (pin "7") (pinfunction "A_7") (pintype "passive"))
      (node (ref "R25") (pin "2") (pinfunction "2_2") (pintype "passive"))
    )
    (net (code "71") (name "Net-(OK3D-COL)") (class "Default")
      (node (ref "JP1") (pin "4") (pinfunction "4_4") (pintype "passive"))
      (node (ref "OK3") (pin "10") (pinfunction "COL_10") (pintype "passive"))
      (node (ref "R26") (pin "2") (pinfunction "2_2") (pintype "passive"))
    )
    (net (code "72") (name "Net-(OK4A-A)") (class "Default")
      (node (ref "OK4") (pin "1") (pinfunction "A_1") (pintype "passive"))
      (node (ref "R23") (pin "2") (pinfunction "2_2") (pintype "passive"))
    )
    (net (code "73") (name "Net-(OK4A-COL)") (class "Default")
      (node (ref "JP1") (pin "5") (pinfunction "5_5") (pintype "passive"))
      (node (ref "OK4") (pin "16") (pinfunction "COL_16") (pintype "passive"))
      (node (ref "R24") (pin "2") (pinfunction "2_2") (pintype "passive"))
    )
    (net (code "74") (name "Net-(OK4B-A)") (class "Default")
      (node (ref "OK4") (pin "3") (pinfunction "A_3") (pintype "passive"))
      (node (ref "R21") (pin "2") (pinfunction "2_2") (pintype "passive"))
    )
    (net (code "75") (name "Net-(OK4B-COL)") (class "Default")
      (node (ref "JP1") (pin "6") (pinfunction "6_6") (pintype "passive"))
      (node (ref "OK4") (pin "14") (pinfunction "COL_14") (pintype "passive"))
      (node (ref "R22") (pin "2") (pinfunction "2_2") (pintype "passive"))
    )
    (net (code "76") (name "Net-(OK4C-A)") (class "Default")
      (node (ref "OK4") (pin "5") (pinfunction "A_5") (pintype "passive"))
      (node (ref "R19") (pin "2") (pinfunction "2_2") (pintype "passive"))
    )
    (net (code "77") (name "Net-(OK4C-COL)") (class "Default")
      (node (ref "JP1") (pin "7") (pinfunction "7_7") (pintype "passive"))
      (node (ref "OK4") (pin "12") (pinfunction "COL_12") (pintype "passive"))
      (node (ref "R20") (pin "2") (pinfunction "2_2") (pintype "passive"))
    )
    (net (code "78") (name "Net-(OK4D-A)") (class "Default")
      (node (ref "OK4") (pin "7") (pinfunction "A_7") (pintype "passive"))
      (node (ref "R1") (pin "2") (pinfunction "2_2") (pintype "passive"))
    )
    (net (code "79") (name "Net-(OK4D-COL)") (class "Default")
      (node (ref "JP1") (pin "8") (pinfunction "8_8") (pintype "passive"))
      (node (ref "OK4") (pin "10") (pinfunction "COL_10") (pintype "passive"))
      (node (ref "R18") (pin "2") (pinfunction "2_2") (pintype "passive"))
    )
    (net (code "80") (name "Net-(R1-Pad1)") (class "Default")
      (node (ref "R1") (pin "1") (pinfunction "1_1") (pintype "passive"))
      (node (ref "SOCKET_LEFT") (pin "33") (pinfunction "33_33") (pintype "passive"))
    )
    (net (code "81") (name "Net-(R2-Pad1)") (class "Default")
      (node (ref "R2") (pin "1") (pinfunction "1_1") (pintype "passive"))
      (node (ref "SOCKET_LEFT") (pin "2") (pinfunction "2_2") (pintype "passive"))
    )
    (net (code "82") (name "Net-(R4-Pad1)") (class "Default")
      (node (ref "R4") (pin "1") (pinfunction "1_1") (pintype "passive"))
      (node (ref "SOCKET_LEFT") (pin "4") (pinfunction "4_4") (pintype "passive"))
    )
    (net (code "83") (name "Net-(R6-Pad1)") (class "Default")
      (node (ref "R6") (pin "1") (pinfunction "1_1") (pintype "passive"))
      (node (ref "SOCKET_LEFT") (pin "6") (pinfunction "6_6") (pintype "passive"))
    )
    (net (code "84") (name "Net-(R8-Pad1)") (class "Default")
      (node (ref "R8") (pin "1") (pinfunction "1_1") (pintype "passive"))
      (node (ref "SOCKET_LEFT") (pin "8") (pinfunction "8_8") (pintype "passive"))
    )
    (net (code "85") (name "Net-(R10-Pad1)") (class "Default")
      (node (ref "R10") (pin "1") (pinfunction "1_1") (pintype "passive"))
      (node (ref "SOCKET_LEFT") (pin "7") (pinfunction "7_7") (pintype "passive"))
    )
    (net (code "86") (name "Net-(R12-Pad1)") (class "Default")
      (node (ref "R12") (pin "1") (pinfunction "1_1") (pintype "passive"))
      (node (ref "SOCKET_LEFT") (pin "5") (pinfunction "5_5") (pintype "passive"))
    )
    (net (code "87") (name "Net-(R14-Pad1)") (class "Default")
      (node (ref "R14") (pin "1") (pinfunction "1_1") (pintype "passive"))
      (node (ref "SOCKET_LEFT") (pin "3") (pinfunction "3_3") (pintype "passive"))
    )
    (net (code "88") (name "Net-(R16-Pad2)") (class "Default")
      (node (ref "R16") (pin "2") (pinfunction "2_2") (pintype "passive"))
      (node (ref "SOCKET_LEFT") (pin "1") (pinfunction "1_1") (pintype "passive"))
    )
    (net (code "89") (name "Net-(R19-Pad1)") (class "Default")
      (node (ref "R19") (pin "1") (pinfunction "1_1") (pintype "passive"))
      (node (ref "SOCKET_LEFT") (pin "35") (pinfunction "35_35") (pintype "passive"))
    )
    (net (code "90") (name "Net-(R21-Pad1)") (class "Default")
      (node (ref "R21") (pin "1") (pinfunction "1_1") (pintype "passive"))
      (node (ref "SOCKET_LEFT") (pin "37") (pinfunction "37_37") (pintype "passive"))
    )
    (net (code "91") (name "Net-(R23-Pad1)") (class "Default")
      (node (ref "R23") (pin "1") (pinfunction "1_1") (pintype "passive"))
      (node (ref "SOCKET_LEFT") (pin "39") (pinfunction "39_39") (pintype "passive"))
    )
    (net (code "92") (name "Net-(R25-Pad1)") (class "Default")
      (node (ref "R25") (pin "1") (pinfunction "1_1") (pintype "passive"))
      (node (ref "SOCKET_LEFT") (pin "40") (pinfunction "40_40") (pintype "passive"))
    )
    (net (code "93") (name "Net-(R27-Pad1)") (class "Default")
      (node (ref "R27") (pin "1") (pinfunction "1_1") (pintype "passive"))
      (node (ref "SOCKET_LEFT") (pin "38") (pinfunction "38_38") (pintype "passive"))
    )
    (net (code "94") (name "Net-(R29-Pad1)") (class "Default")
      (node (ref "R29") (pin "1") (pinfunction "1_1") (pintype "passive"))
      (node (ref "SOCKET_LEFT") (pin "36") (pinfunction "36_36") (pintype "passive"))
    )
    (net (code "95") (name "Net-(R31-Pad1)") (class "Default")
      (node (ref "R31") (pin "1") (pinfunction "1_1") (pintype "passive"))
      (node (ref "SOCKET_LEFT") (pin "34") (pinfunction "34_34") (pintype "passive"))
    )
    (net (code "96") (name "unconnected-(QCM1-Pad2)") (class "Default")
      (node (ref "QCM1") (pin "2") (pinfunction "2_2") (pintype "passive"))
    )
    (net (code "97") (name "unconnected-(QCM2-Pad2)") (class "Default")
      (node (ref "QCM2") (pin "2") (pinfunction "2_2") (pintype "passive"))
    )
    (net (code "98") (name "unconnected-(QCM3-Pad2)") (class "Default")
      (node (ref "QCM3") (pin "2") (pinfunction "2_2") (pintype "passive"))
    )
    (net (code "99") (name "unconnected-(QCM4-Pad2)") (class "Default")
      (node (ref "QCM4") (pin "2") (pinfunction "2_2") (pintype "passive"))
    )
    (net (code "100") (name "unconnected-(QCM5-Pad2)") (class "Default")
      (node (ref "QCM5") (pin "2") (pinfunction "2_2") (pintype "passive"))
    )
    (net (code "101") (name "unconnected-(QCM6-Pad2)") (class "Default")
      (node (ref "QCM6") (pin "2") (pinfunction "2_2") (pintype "passive"))
    )
    (net (code "102") (name "unconnected-(QCM7-Pad2)") (class "Default")
      (node (ref "QCM7") (pin "2") (pinfunction "2_2") (pintype "passive"))
    )
    (net (code "103") (name "unconnected-(QCM8-Pad2)") (class "Default")
      (node (ref "QCM8") (pin "2") (pinfunction "2_2") (pintype "passive"))
    )
    (net (code "104") (name "unconnected-(SOCKET_LEFT-Pad9)") (class "Default")
      (node (ref "SOCKET_LEFT") (pin "9") (pinfunction "9_9") (pintype "passive"))
    )
    (net (code "105") (name "unconnected-(SOCKET_LEFT-Pad10)") (class "Default")
      (node (ref "SOCKET_LEFT") (pin "10") (pinfunction "10_10") (pintype "passive"))
    )
    (net (code "106") (name "unconnected-(SOCKET_LEFT-Pad11)") (class "Default")
      (node (ref "SOCKET_LEFT") (pin "11") (pinfunction "11_11") (pintype "passive"))
    )
    (net (code "107") (name "unconnected-(SOCKET_LEFT-Pad12)") (class "Default")
      (node (ref "SOCKET_LEFT") (pin "12") (pinfunction "12_12") (pintype "passive"))
    )
    (net (code "108") (name "unconnected-(SOCKET_LEFT-Pad13)") (class "Default")
      (node (ref "SOCKET_LEFT") (pin "13") (pinfunction "13_13") (pintype "passive"))
    )
    (net (code "109") (name "unconnected-(SOCKET_LEFT-Pad14)") (class "Default")
      (node (ref "SOCKET_LEFT") (pin "14") (pinfunction "14_14") (pintype "passive"))
    )
    (net (code "110") (name "unconnected-(SOCKET_LEFT-Pad15)") (class "Default")
      (node (ref "SOCKET_LEFT") (pin "15") (pinfunction "15_15") (pintype "passive"))
    )
    (net (code "111") (name "unconnected-(SOCKET_LEFT-Pad16)") (class "Default")
      (node (ref "SOCKET_LEFT") (pin "16") (pinfunction "16_16") (pintype "passive"))
    )
    (net (code "112") (name "unconnected-(SOCKET_LEFT-Pad17)") (class "Default")
      (node (ref "SOCKET_LEFT") (pin "17") (pinfunction "17_17") (pintype "passive"))
    )
    (net (code "113") (name "unconnected-(SOCKET_LEFT-Pad18)") (class "Default")
      (node (ref "SOCKET_LEFT") (pin "18") (pinfunction "18_18") (pintype "passive"))
    )
    (net (code "114") (name "unconnected-(SOCKET_LEFT-Pad19)") (class "Default")
      (node (ref "SOCKET_LEFT") (pin "19") (pinfunction "19_19") (pintype "passive"))
    )
    (net (code "115") (name "unconnected-(SOCKET_LEFT-Pad20)") (class "Default")
      (node (ref "SOCKET_LEFT") (pin "20") (pinfunction "20_20") (pintype "passive"))
    )
    (net (code "116") (name "unconnected-(SOCKET_LEFT-Pad22)") (class "Default")
      (node (ref "SOCKET_LEFT") (pin "22") (pinfunction "22_22") (pintype "passive"))
    )
    (net (code "117") (name "unconnected-(SOCKET_LEFT-Pad23)") (class "Default")
      (node (ref "SOCKET_LEFT") (pin "23") (pinfunction "23_23") (pintype "passive"))
    )
    (net (code "118") (name "unconnected-(SOCKET_LEFT-Pad24)") (class "Default")
      (node (ref "SOCKET_LEFT") (pin "24") (pinfunction "24_24") (pintype "passive"))
    )
    (net (code "119") (name "unconnected-(SOCKET_LEFT-Pad25)") (class "Default")
      (node (ref "SOCKET_LEFT") (pin "25") (pinfunction "25_25") (pintype "passive"))
    )
    (net (code "120") (name "unconnected-(SOCKET_LEFT-Pad26)") (class "Default")
      (node (ref "SOCKET_LEFT") (pin "26") (pinfunction "26_26") (pintype "passive"))
    )
    (net (code "121") (name "unconnected-(SOCKET_LEFT-Pad27)") (class "Default")
      (node (ref "SOCKET_LEFT") (pin "27") (pinfunction "27_27") (pintype "passive"))
    )
    (net (code "122") (name "unconnected-(SOCKET_LEFT-Pad28)") (class "Default")
      (node (ref "SOCKET_LEFT") (pin "28") (pinfunction "28_28") (pintype "passive"))
    )
    (net (code "123") (name "unconnected-(SOCKET_LEFT-Pad29)") (class "Default")
      (node (ref "SOCKET_LEFT") (pin "29") (pinfunction "29_29") (pintype "passive"))
    )
    (net (code "124") (name "unconnected-(SOCKET_LEFT-Pad30)") (class "Default")
      (node (ref "SOCKET_LEFT") (pin "30") (pinfunction "30_30") (pintype "passive"))
    )
    (net (code "125") (name "unconnected-(SOCKET_LEFT-Pad31)") (class "Default")
      (node (ref "SOCKET_LEFT") (pin "31") (pinfunction "31_31") (pintype "passive"))
    )
    (net (code "126") (name "unconnected-(SOCKET_LEFT-Pad32)") (class "Default")
      (node (ref "SOCKET_LEFT") (pin "32") (pinfunction "32_32") (pintype "passive"))
    )
    (net (code "127") (name "unconnected-(SOCKET_RIGHT-Pad3)") (class "Default")
      (node (ref "SOCKET_RIGHT") (pin "3") (pinfunction "3_3") (pintype "passive"))
    )
    (net (code "128") (name "unconnected-(SOCKET_RIGHT-Pad4)") (class "Default")
      (node (ref "SOCKET_RIGHT") (pin "4") (pinfunction "4_4") (pintype "passive"))
    )
    (net (code "129") (name "unconnected-(SOCKET_RIGHT-Pad9)") (class "Default")
      (node (ref "SOCKET_RIGHT") (pin "9") (pinfunction "9_9") (pintype "passive"))
    )
    (net (code "130") (name "unconnected-(SOCKET_RIGHT-Pad11)") (class "Default")
      (node (ref "SOCKET_RIGHT") (pin "11") (pinfunction "11_11") (pintype "passive"))
    )
    (net (code "131") (name "unconnected-(SOCKET_RIGHT-Pad12)") (class "Default")
      (node (ref "SOCKET_RIGHT") (pin "12") (pinfunction "12_12") (pintype "passive"))
    )
    (net (code "132") (name "unconnected-(SOCKET_RIGHT-Pad13)") (class "Default")
      (node (ref "SOCKET_RIGHT") (pin "13") (pinfunction "13_13") (pintype "passive"))
    )
    (net (code "133") (name "unconnected-(SOCKET_RIGHT-Pad15)") (class "Default")
      (node (ref "SOCKET_RIGHT") (pin "15") (pinfunction "15_15") (pintype "passive"))
    )
    (net (code "134") (name "unconnected-(SOCKET_RIGHT-Pad17)") (class "Default")
      (node (ref "SOCKET_RIGHT") (pin "17") (pinfunction "17_17") (pintype "passive"))
    )
    (net (code "135") (name "unconnected-(SOCKET_RIGHT-Pad19)") (class "Default")
      (node (ref "SOCKET_RIGHT") (pin "19") (pinfunction "19_19") (pintype "passive"))
    )
    (net (code "136") (name "unconnected-(SOCKET_RIGHT-Pad21)") (class "Default")
      (node (ref "SOCKET_RIGHT") (pin "21") (pinfunction "21_21") (pintype "passive"))
    )
    (net (code "137") (name "unconnected-(SOCKET_RIGHT-Pad23)") (class "Default")
      (node (ref "SOCKET_RIGHT") (pin "23") (pinfunction "23_23") (pintype "passive"))
    )
    (net (code "138") (name "unconnected-(SOCKET_RIGHT-Pad25)") (class "Default")
      (node (ref "SOCKET_RIGHT") (pin "25") (pinfunction "25_25") (pintype "passive"))
    )
    (net (code "139") (name "unconnected-(SOCKET_RIGHT-Pad27)") (class "Default")
      (node (ref "SOCKET_RIGHT") (pin "27") (pinfunction "27_27") (pintype "passive"))
    )
    (net (code "140") (name "unconnected-(SOCKET_RIGHT-Pad28)") (class "Default")
      (node (ref "SOCKET_RIGHT") (pin "28") (pinfunction "28_28") (pintype "passive"))
    )
    (net (code "141") (name "unconnected-(SOCKET_RIGHT-Pad29)") (class "Default")
      (node (ref "SOCKET_RIGHT") (pin "29") (pinfunction "29_29") (pintype "passive"))
    )
    (net (code "142") (name "unconnected-(SOCKET_RIGHT-Pad30)") (class "Default")
      (node (ref "SOCKET_RIGHT") (pin "30") (pinfunction "30_30") (pintype "passive"))
    )
    (net (code "143") (name "unconnected-(SOCKET_RIGHT-Pad31)") (class "Default")
      (node (ref "SOCKET_RIGHT") (pin "31") (pinfunction "31_31") (pintype "passive"))
    )
    (net (code "144") (name "unconnected-(SOCKET_RIGHT-Pad32)") (class "Default")
      (node (ref "SOCKET_RIGHT") (pin "32") (pinfunction "32_32") (pintype "passive"))
    )
    (net (code "145") (name "unconnected-(U1-1OUT-Pad1)") (class "Default")
      (node (ref "U1") (pin "1") (pinfunction "1OUT_1") (pintype "output"))
    )
    (net (code "146") (name "unconnected-(U1-2IN--Pad6)") (class "Default")
      (node (ref "U1") (pin "6") (pinfunction "2IN-_6") (pintype "input"))
    )
    (net (code "147") (name "unconnected-(U1-2OUT-Pad7)") (class "Default")
      (node (ref "U1") (pin "7") (pinfunction "2OUT_7") (pintype "output"))
    )
    (net (code "148") (name "unconnected-(U2-1OUT-Pad1)") (class "Default")
      (node (ref "U2") (pin "1") (pinfunction "1OUT_1") (pintype "output"))
    )
    (net (code "149") (name "unconnected-(U2-2IN--Pad6)") (class "Default")
      (node (ref "U2") (pin "6") (pinfunction "2IN-_6") (pintype "input"))
    )
    (net (code "150") (name "unconnected-(U2-2OUT-Pad7)") (class "Default")
      (node (ref "U2") (pin "7") (pinfunction "2OUT_7") (pintype "output"))
    )
    (net (code "151") (name "unconnected-(U3-1OUT-Pad1)") (class "Default")
      (node (ref "U3") (pin "1") (pinfunction "1OUT_1") (pintype "output"))
    )
    (net (code "152") (name "unconnected-(U3-2IN--Pad6)") (class "Default")
      (node (ref "U3") (pin "6") (pinfunction "2IN-_6") (pintype "input"))
    )
    (net (code "153") (name "unconnected-(U3-2OUT-Pad7)") (class "Default")
      (node (ref "U3") (pin "7") (pinfunction "2OUT_7") (pintype "output"))
    )
    (net (code "154") (name "unconnected-(U4-1OUT-Pad1)") (class "Default")
      (node (ref "U4") (pin "1") (pinfunction "1OUT_1") (pintype "output"))
    )
    (net (code "155") (name "unconnected-(U4-2IN--Pad6)") (class "Default")
      (node (ref "U4") (pin "6") (pinfunction "2IN-_6") (pintype "input"))
    )
    (net (code "156") (name "unconnected-(U4-2OUT-Pad7)") (class "Default")
      (node (ref "U4") (pin "7") (pinfunction "2OUT_7") (pintype "output"))
    )
    (net (code "157") (name "unconnected-(U5-1OUT-Pad1)") (class "Default")
      (node (ref "U5") (pin "1") (pinfunction "1OUT_1") (pintype "output"))
    )
    (net (code "158") (name "unconnected-(U5-2IN--Pad6)") (class "Default")
      (node (ref "U5") (pin "6") (pinfunction "2IN-_6") (pintype "input"))
    )
    (net (code "159") (name "unconnected-(U5-2OUT-Pad7)") (class "Default")
      (node (ref "U5") (pin "7") (pinfunction "2OUT_7") (pintype "output"))
    )
    (net (code "160") (name "unconnected-(U6-1OUT-Pad1)") (class "Default")
      (node (ref "U6") (pin "1") (pinfunction "1OUT_1") (pintype "output"))
    )
    (net (code "161") (name "unconnected-(U6-2IN--Pad6)") (class "Default")
      (node (ref "U6") (pin "6") (pinfunction "2IN-_6") (pintype "input"))
    )
    (net (code "162") (name "unconnected-(U6-2OUT-Pad7)") (class "Default")
      (node (ref "U6") (pin "7") (pinfunction "2OUT_7") (pintype "output"))
    )
    (net (code "163") (name "unconnected-(U7-1OUT-Pad1)") (class "Default")
      (node (ref "U7") (pin "1") (pinfunction "1OUT_1") (pintype "output"))
    )
    (net (code "164") (name "unconnected-(U7-2IN--Pad6)") (class "Default")
      (node (ref "U7") (pin "6") (pinfunction "2IN-_6") (pintype "input"))
    )
    (net (code "165") (name "unconnected-(U7-2OUT-Pad7)") (class "Default")
      (node (ref "U7") (pin "7") (pinfunction "2OUT_7") (pintype "output"))
    )
    (net (code "166") (name "unconnected-(U8-1OUT-Pad1)") (class "Default")
      (node (ref "U8") (pin "1") (pinfunction "1OUT_1") (pintype "output"))
    )
    (net (code "167") (name "unconnected-(U8-2IN--Pad6)") (class "Default")
      (node (ref "U8") (pin "6") (pinfunction "2IN-_6") (pintype "input"))
    )
    (net (code "168") (name "unconnected-(U8-2OUT-Pad7)") (class "Default")
      (node (ref "U8") (pin "7") (pinfunction "2OUT_7") (pintype "output"))
    )
  )
)
